# light_sensor_basic.net
KiCad netlist of a schematic drawn in EAGLE
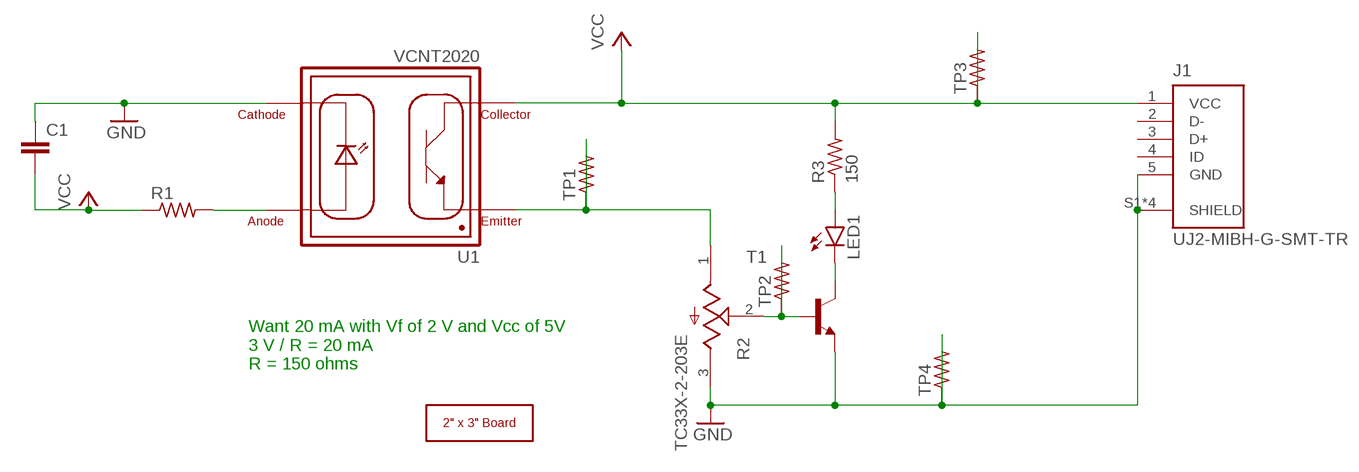
[diagram p0: schematic, sheet 1]

(export (version "E")
  (design (tool "Eeschema 10.0.6"))
  (components
    (comp (ref "C1")
      (value "C-EUC1206")
      (footprint "eagle-import:C1206")
      (libsource (lib "eagle-import") (part "C-EUC1206"))
    )
    (comp (ref "J1")
      (value "UJ2-MIBH-G-SMT-TR")
      (footprint "eagle-import:CUI_UJ2-MIBH-G-SMT-TR")
      (fields (field (name "MANUFACTURER") "CUI"))
      (libsource (lib "eagle-import") (part "UJ2-MIBH-G-SMT-TR"))
    )
    (comp (ref "LED1")
      (value "LEDSML0805")
      (footprint "eagle-import:SML0805")
      (libsource (lib "eagle-import") (part "LEDSML0805"))
    )
    (comp (ref "R1")
      (value "R-US_R1206")
      (footprint "eagle-import:R1206")
      (libsource (lib "eagle-import") (part "R-US_R1206"))
    )
    (comp (ref "R2")
      (value "TC33X-2-203E")
      (footprint "eagle-import:TRIM_TC33X-2-203E")
      (fields (field (name "DIGIKEY_PART_NUMBER") "TC33X-2-203ETR-ND") (field (name "MF") "Bourns"))
      (libsource (lib "eagle-import") (part "TC33X-2-203E"))
    )
    (comp (ref "R3")
      (value "150")
      (footprint "eagle-import:R0805")
      (libsource (lib "eagle-import") (part "R-US_R0805"))
    )
    (comp (ref "T1")
      (value "-NPN-SOT23-EBC")
      (footprint "eagle-import:SOT23-EBC")
      (libsource (lib "eagle-import") (part "-NPN-SOT23-EBC"))
    )
    (comp (ref "TP1")
      (value "R-US_R1206")
      (footprint "eagle-import:R1206")
      (libsource (lib "eagle-import") (part "R-US_R1206"))
    )
    (comp (ref "TP2")
      (value "R-US_R1206")
      (footprint "eagle-import:R1206")
      (libsource (lib "eagle-import") (part "R-US_R1206"))
    )
    (comp (ref "TP3")
      (value "R-US_R1206")
      (footprint "eagle-import:R1206")
      (libsource (lib "eagle-import") (part "R-US_R1206"))
    )
    (comp (ref "TP4")
      (value "R-US_R1206")
      (footprint "eagle-import:R1206")
      (libsource (lib "eagle-import") (part "R-US_R1206"))
    )
    (comp (ref "U$1")
      (value "2X3_BOARD_V2")
      (footprint "eagle-import:2X3_BOARD_V2")
      (libsource (lib "eagle-import") (part "2X3_BOARD_V2"))
    )
    (comp (ref "U1")
      (value "VCNT2020")
      (footprint "eagle-import:XDCR_VCNT2020")
      (fields (field (name "DIGIKEY_PART_NUMBER") "VCNT2020TR-ND") (field (name "MF") "Vishay"))
      (libsource (lib "eagle-import") (part "VCNT2020"))
    )
  )
  (nets
    (net (code "1") (name "GND") (class "Default")
      (node (ref "C1") (pin "1") (pinfunction "1_1") (pintype "passive"))
      (node (ref "J1") (pin "5") (pinfunction "GND_5") (pintype "power_in"))
      (node (ref "J1") (pin "S1") (pinfunction "SHIELD_S1") (pintype "passive"))
      (node (ref "J1") (pin "S2") (pinfunction "SHIELD_S2") (pintype "passive"))
      (node (ref "J1") (pin "S3") (pinfunction "SHIELD_S3") (pintype "passive"))
      (node (ref "J1") (pin "S4") (pinfunction "SHIELD_S4") (pintype "passive"))
      (node (ref "R2") (pin "3") (pinfunction "CW_3") (pintype "passive"))
      (node (ref "T1") (pin "E") (pinfunction "E_E") (pintype "passive"))
      (node (ref "TP4") (pin "1") (pinfunction "1_1") (pintype "passive"))
      (node (ref "TP4") (pin "2") (pinfunction "2_2") (pintype "passive"))
      (node (ref "U1") (pin "4") (pinfunction "CATHODE_4") (pintype "passive"))
    )
    (net (code "2") (name "Net-(LED1-PadA)") (class "Default")
      (node (ref "LED1") (pin "A") (pinfunction "A_A") (pintype "passive"))
      (node (ref "R3") (pin "1") (pinfunction "1_1") (pintype "passive"))
    )
    (net (code "3") (name "Net-(LED1-PadC)") (class "Default")
      (node (ref "LED1") (pin "C") (pinfunction "C_C") (pintype "passive"))
      (node (ref "T1") (pin "C") (pinfunction "C_C") (pintype "passive"))
    )
    (net (code "4") (name "Net-(R2-CCW)") (class "Default")
      (node (ref "R2") (pin "1") (pinfunction "CCW_1") (pintype "passive"))
      (node (ref "TP1") (pin "1") (pinfunction "1_1") (pintype "passive"))
      (node (ref "TP1") (pin "2") (pinfunction "2_2") (pintype "passive"))
      (node (ref "U1") (pin "1") (pinfunction "EMITTER_1") (pintype "passive"))
    )
    (net (code "5") (name "Net-(R2-W)") (class "Default")
      (node (ref "R2") (pin "2") (pinfunction "W_2") (pintype "passive"))
      (node (ref "T1") (pin "B") (pinfunction "B_B") (pintype "passive"))
      (node (ref "TP2") (pin "1") (pinfunction "1_1") (pintype "passive"))
      (node (ref "TP2") (pin "2") (pinfunction "2_2") (pintype "passive"))
    )
    (net (code "6") (name "Net-(U1-ANODE)") (class "Default")
      (node (ref "R1") (pin "2") (pinfunction "2_2") (pintype "passive"))
      (node (ref "U1") (pin "3") (pinfunction "ANODE_3") (pintype "passive"))
    )
    (net (code "7") (name "VCC") (class "Default")
      (node (ref "C1") (pin "2") (pinfunction "2_2") (pintype "passive"))
      (node (ref "J1") (pin "1") (pinfunction "VCC_1") (pintype "power_in"))
      (node (ref "R1") (pin "1") (pinfunction "1_1") (pintype "passive"))
      (node (ref "R3") (pin "2") (pinfunction "2_2") (pintype "passive"))
      (node (ref "TP3") (pin "1") (pinfunction "1_1") (pintype "passive"))
      (node (ref "TP3") (pin "2") (pinfunction "2_2") (pintype "passive"))
      (node (ref "U1") (pin "2") (pinfunction "COLLECTOR_2") (pintype "passive"))
    )
    (net (code "8") (name "unconnected-(J1-D+-Pad3)") (class "Default")
      (node (ref "J1") (pin "3") (pinfunction "D+_3") (pintype "bidirectional"))
    )
    (net (code "9") (name "unconnected-(J1-D--Pad2)") (class "Default")
      (node (ref "J1") (pin "2") (pinfunction "D-_2") (pintype "bidirectional"))
    )
    (net (code "10") (name "unconnected-(J1-ID-Pad4)") (class "Default")
      (node (ref "J1") (pin "4") (pinfunction "ID_4") (pintype "bidirectional"))
    )
  )
)
